# Schematic.net
KiCad netlist of a schematic drawn in Altium Designer
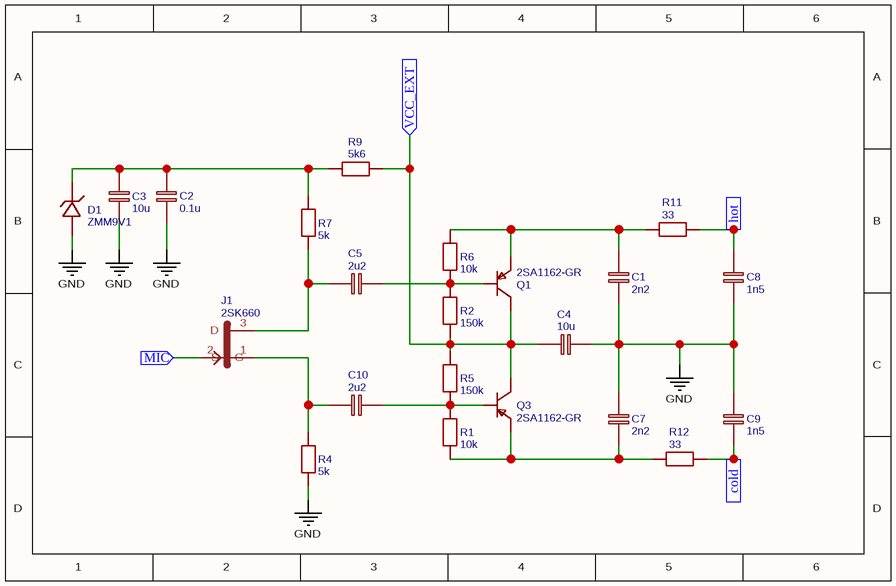
[diagram p0: Schematic.schdoc]

(export (version "E")
  (design (tool "Eeschema 10.0.6"))
  (components
    (comp (ref "C1")
      (value "2n2")
      (fields
        (field (name "MANUFACTURER PART") "0603B222K500NT")
        (field (name "MANUFACTURER") "FH(风华)")
        (field (name "CONTRIBUTOR") "LCEDA_Lib")
      )
      (libsource (lib "altium-import") (part "root_1_2n2_"))
    )
    (comp (ref "C2")
      (value "0.1u")
      (fields
        (field (name "MANUFACTURER PART") "CC0603KRX7R9BB104")
        (field (name "MANUFACTURER") "YAGEO(国巨)")
        (field (name "CONTRIBUTOR") "LCEDA_Lib")
      )
      (libsource (lib "altium-import") (part "root_1_0.1u_"))
    )
    (comp (ref "C3")
      (value "10u")
      (fields
        (field (name "MANUFACTURER PART") "CL31A106KBHNNNE")
        (field (name "MANUFACTURER") "SAMSUNG(三星)")
        (field (name "CONTRIBUTOR") "LCEDA_Lib")
      )
      (libsource (lib "altium-import") (part "root_1_10u_"))
    )
    (comp (ref "C4")
      (value "10u")
      (fields
        (field (name "MANUFACTURER PART") "CL31A106KBHNNNE")
        (field (name "MANUFACTURER") "SAMSUNG(三星)")
        (field (name "CONTRIBUTOR") "LCEDA_Lib")
      )
      (libsource (lib "altium-import") (part "root_2_10u_"))
    )
    (comp (ref "C5")
      (value "2u2")
      (fields
        (field (name "MANUFACTURER PART") "CL10A225KO8NNNC")
        (field (name "MANUFACTURER") "SAMSUNG(三星)")
        (field (name "CONTRIBUTOR") "LCEDA_Lib")
      )
      (libsource (lib "altium-import") (part "root_2_2u2_"))
    )
    (comp (ref "C7")
      (value "2n2")
      (fields
        (field (name "MANUFACTURER PART") "0603B222K500NT")
        (field (name "MANUFACTURER") "FH(风华)")
        (field (name "CONTRIBUTOR") "LCEDA_Lib")
      )
      (libsource (lib "altium-import") (part "root_1_2n2_"))
    )
    (comp (ref "C8")
      (value "1n5")
      (fields
        (field (name "MANUFACTURER PART") "CL10B152KB8NNNC")
        (field (name "MANUFACTURER") "SAMSUNG(三星)")
        (field (name "CONTRIBUTOR") "LCEDA_Lib")
      )
      (libsource (lib "altium-import") (part "root_1_1n5_"))
    )
    (comp (ref "C9")
      (value "1n5")
      (fields
        (field (name "MANUFACTURER PART") "CL10B152KB8NNNC")
        (field (name "MANUFACTURER") "SAMSUNG(三星)")
        (field (name "CONTRIBUTOR") "LCEDA_Lib")
      )
      (libsource (lib "altium-import") (part "root_1_1n5_"))
    )
    (comp (ref "C10")
      (value "2u2")
      (fields
        (field (name "MANUFACTURER PART") "CL10A225KO8NNNC")
        (field (name "MANUFACTURER") "SAMSUNG(三星)")
        (field (name "CONTRIBUTOR") "LCEDA_Lib")
      )
      (libsource (lib "altium-import") (part "root_2_2u2_"))
    )
    (comp (ref "D1")
      (value "ZMM9V1")
      (fields (field (name "MANUFACTURER") "YONGYUTAI(永裕泰)"))
      (libsource (lib "altium-import") (part "root_3_ZMM9V1_"))
    )
    (comp (ref "J1")
      (value "2SK660")
      (fields (field (name "CONTRIBUTOR") "rayindra.panandita"))
      (libsource (lib "altium-import") (part "root_0_2SK660_"))
    )
    (comp (ref "Q1")
      (value "2SA1162-GR")
      (fields
        (field (name "MANUFACTURER") "CJ(江苏长电/长晶)")
        (field (name "MANUFACTURER PART") "2SA1162(RANGE:200-400)")
      )
      (libsource (lib "") (part "root_0_2SA1162-GR__1"))
    )
    (comp (ref "Q3")
      (value "2SA1162-GR")
      (fields
        (field (name "MANUFACTURER") "CJ(江苏长电/长晶)")
        (field (name "MANUFACTURER PART") "2SA1162(RANGE:200-400)")
      )
      (libsource (lib "altium-import") (part "root_0_2SA1162-GR_"))
    )
    (comp (ref "R1")
      (value "10k")
      (fields
        (field (name "MANUFACTURER PART") "0603WAF1002T5E")
        (field (name "MANUFACTURER") "UNI-ROYAL(厚声)")
        (field (name "CONTRIBUTOR") "LCEDA_Lib")
      )
      (libsource (lib "altium-import") (part "root_3_10k_"))
    )
    (comp (ref "R2")
      (value "150k")
      (fields
        (field (name "MANUFACTURER PART") "0603WAF1503T5E")
        (field (name "MANUFACTURER") "UNI-ROYAL(厚声)")
        (field (name "CONTRIBUTOR") "LCEDA_Lib")
      )
      (libsource (lib "altium-import") (part "root_3_150k_"))
    )
    (comp (ref "R4")
      (value "5k")
      (fields
        (field (name "MANUFACTURER PART") "0603WAF5601T5E")
        (field (name "MANUFACTURER") "UNI-ROYAL(厚声)")
        (field (name "CONTRIBUTOR") "LCEDA_Lib")
      )
      (libsource (lib "altium-import") (part "root_3_5k_"))
    )
    (comp (ref "R5")
      (value "150k")
      (fields
        (field (name "MANUFACTURER PART") "0603WAF1503T5E")
        (field (name "MANUFACTURER") "UNI-ROYAL(厚声)")
        (field (name "CONTRIBUTOR") "LCEDA_Lib")
      )
      (libsource (lib "altium-import") (part "root_3_150k_"))
    )
    (comp (ref "R6")
      (value "10k")
      (fields
        (field (name "MANUFACTURER PART") "0603WAF1002T5E")
        (field (name "MANUFACTURER") "UNI-ROYAL(厚声)")
        (field (name "CONTRIBUTOR") "LCEDA_Lib")
      )
      (libsource (lib "altium-import") (part "root_3_10k_"))
    )
    (comp (ref "R7")
      (value "5k")
      (fields
        (field (name "MANUFACTURER PART") "0603WAF5601T5E")
        (field (name "MANUFACTURER") "UNI-ROYAL(厚声)")
        (field (name "CONTRIBUTOR") "LCEDA_Lib")
      )
      (libsource (lib "altium-import") (part "root_3_5k_"))
    )
    (comp (ref "R9")
      (value "5k6")
      (fields
        (field (name "MANUFACTURER PART") "0603WAF5601T5E")
        (field (name "MANUFACTURER") "UNI-ROYAL(厚声)")
        (field (name "CONTRIBUTOR") "LCEDA_Lib")
      )
      (libsource (lib "altium-import") (part "root_2_5k6_"))
    )
    (comp (ref "R11")
      (value "33")
      (fields
        (field (name "MANUFACTURER PART") "0603WAF3303T5E")
        (field (name "MANUFACTURER") "UNI-ROYAL(厚声)")
        (field (name "CONTRIBUTOR") "LCEDA_Lib")
      )
      (libsource (lib "altium-import") (part "root_0_33_"))
    )
    (comp (ref "R12")
      (value "33")
      (fields
        (field (name "MANUFACTURER PART") "0603WAF3303T5E")
        (field (name "MANUFACTURER") "UNI-ROYAL(厚声)")
        (field (name "CONTRIBUTOR") "LCEDA_Lib")
      )
      (libsource (lib "altium-import") (part "root_0_33_"))
    )
  )
  (nets
    (net (code "1") (name "/MIC") (class "Default")
      (node (ref "J1") (pin "2") (pinfunction "G_2") (pintype "passive"))
    )
    (net (code "2") (name "/VCC_EXT") (class "Default")
      (node (ref "C4") (pin "2") (pinfunction "2_2") (pintype "passive"))
      (node (ref "Q1") (pin "3") (pinfunction "3_3") (pintype "passive"))
      (node (ref "Q3") (pin "3") (pinfunction "3_3") (pintype "passive"))
      (node (ref "R2") (pin "2") (pinfunction "2_2") (pintype "passive"))
      (node (ref "R5") (pin "1") (pinfunction "1_1") (pintype "passive"))
      (node (ref "R9") (pin "1") (pinfunction "1_1") (pintype "passive"))
    )
    (net (code "3") (name "/cold") (class "Default")
      (node (ref "C9") (pin "1") (pinfunction "1_1") (pintype "passive"))
      (node (ref "R12") (pin "2") (pinfunction "2_2") (pintype "passive"))
    )
    (net (code "4") (name "/hot") (class "Default")
      (node (ref "C8") (pin "2") (pinfunction "2_2") (pintype "passive"))
      (node (ref "R11") (pin "2") (pinfunction "2_2") (pintype "passive"))
    )
    (net (code "5") (name "GND") (class "Default")
      (node (ref "C1") (pin "1") (pinfunction "1_1") (pintype "passive"))
      (node (ref "C2") (pin "1") (pinfunction "1_1") (pintype "passive"))
      (node (ref "C3") (pin "1") (pinfunction "1_1") (pintype "passive"))
      (node (ref "C4") (pin "1") (pinfunction "1_1") (pintype "passive"))
      (node (ref "C7") (pin "2") (pinfunction "2_2") (pintype "passive"))
      (node (ref "C8") (pin "1") (pinfunction "1_1") (pintype "passive"))
      (node (ref "C9") (pin "2") (pinfunction "2_2") (pintype "passive"))
      (node (ref "D1") (pin "2") (pinfunction "A_2") (pintype "passive"))
      (node (ref "R4") (pin "2") (pinfunction "2_2") (pintype "passive"))
    )
    (net (code "6") (name "Net-(C1-Pad2)") (class "Default")
      (node (ref "C1") (pin "2") (pinfunction "2_2") (pintype "passive"))
      (node (ref "Q1") (pin "2") (pinfunction "2_2") (pintype "passive"))
      (node (ref "R11") (pin "1") (pinfunction "1_1") (pintype "passive"))
      (node (ref "R6") (pin "1") (pinfunction "1_1") (pintype "passive"))
    )
    (net (code "7") (name "Net-(C5-Pad1)") (class "Default")
      (node (ref "C5") (pin "1") (pinfunction "1_1") (pintype "passive"))
      (node (ref "Q1") (pin "1") (pinfunction "1_1") (pintype "passive"))
      (node (ref "R2") (pin "1") (pinfunction "1_1") (pintype "passive"))
      (node (ref "R6") (pin "2") (pinfunction "2_2") (pintype "passive"))
    )
    (net (code "8") (name "Net-(C7-Pad1)") (class "Default")
      (node (ref "C7") (pin "1") (pinfunction "1_1") (pintype "passive"))
      (node (ref "Q3") (pin "2") (pinfunction "2_2") (pintype "passive"))
      (node (ref "R1") (pin "2") (pinfunction "2_2") (pintype "passive"))
      (node (ref "R12") (pin "1") (pinfunction "1_1") (pintype "passive"))
    )
    (net (code "9") (name "Net-(C10-Pad1)") (class "Default")
      (node (ref "C10") (pin "1") (pinfunction "1_1") (pintype "passive"))
      (node (ref "Q3") (pin "1") (pinfunction "1_1") (pintype "passive"))
      (node (ref "R1") (pin "1") (pinfunction "1_1") (pintype "passive"))
      (node (ref "R5") (pin "2") (pinfunction "2_2") (pintype "passive"))
    )
    (net (code "10") (name "Net-(D1-C)") (class "Default")
      (node (ref "C2") (pin "2") (pinfunction "2_2") (pintype "passive"))
      (node (ref "C3") (pin "2") (pinfunction "2_2") (pintype "passive"))
      (node (ref "D1") (pin "1") (pinfunction "C_1") (pintype "passive"))
      (node (ref "R7") (pin "1") (pinfunction "1_1") (pintype "passive"))
      (node (ref "R9") (pin "2") (pinfunction "2_2") (pintype "passive"))
    )
    (net (code "11") (name "Net-(J1-D)") (class "Default")
      (node (ref "C5") (pin "2") (pinfunction "2_2") (pintype "passive"))
      (node (ref "J1") (pin "3") (pinfunction "D_3") (pintype "passive"))
      (node (ref "R7") (pin "2") (pinfunction "2_2") (pintype "passive"))
    )
    (net (code "12") (name "Net-(J1-S)") (class "Default")
      (node (ref "C10") (pin "2") (pinfunction "2_2") (pintype "passive"))
      (node (ref "J1") (pin "1") (pinfunction "S_1") (pintype "passive"))
      (node (ref "R4") (pin "1") (pinfunction "1_1") (pintype "passive"))
    )
  )
)
